# INCAM.net
KiCad netlist of a schematic drawn in Altium Designer
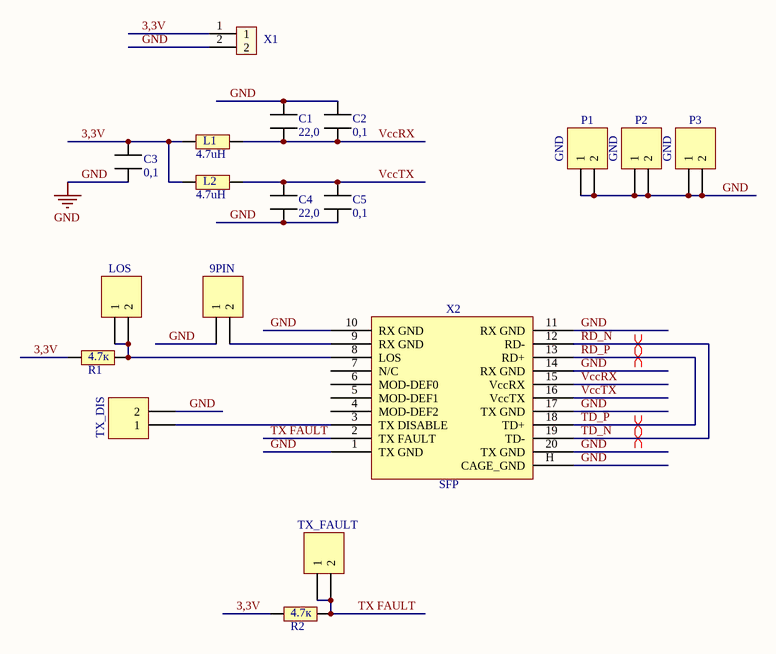
[diagram p0: INCAM.SchDoc]

(export (version "E")
  (design (tool "Eeschema 10.0.6"))
  (components
    (comp (ref "9PIN")
      (value "Header 2")
      (footprint "HDR1X2")
      (description "Header, 2-Pin")
      (fields (field (name "PUBLISHER") "Altium Limited"))
      (libsource (lib "Miscellaneous Connectors") (part "Header 2"))
    )
    (comp (ref "C1") (value "22,0") (footprint "Cap_BIG") (libsource (lib "Schlib") (part "CAP_BIG")))
    (comp (ref "C2") (value "0,1") (footprint "CAP_SMALL") (libsource (lib "Schlib") (part "CAP_SMALL")))
    (comp (ref "C3") (value "0,1") (footprint "CAP_SMALL") (libsource (lib "Schlib") (part "CAP_SMALL")))
    (comp (ref "C4") (value "22,0") (footprint "Cap_BIG") (libsource (lib "Schlib") (part "CAP_BIG")))
    (comp (ref "C5") (value "0,1") (footprint "CAP_SMALL") (libsource (lib "Schlib") (part "CAP_SMALL")))
    (comp (ref "L1") (value "4.7uH") (footprint "RES") (libsource (lib "Schlib") (part "RES")))
    (comp (ref "L2") (value "4.7uH") (footprint "RES") (libsource (lib "Schlib") (part "RES")))
    (comp (ref "LOS")
      (value "Header 2")
      (footprint "HDR1X2")
      (description "Header, 2-Pin")
      (fields (field (name "PUBLISHER") "Altium Limited"))
      (libsource (lib "Miscellaneous Connectors") (part "Header 2"))
    )
    (comp (ref "P1")
      (value "GND")
      (footprint "HDR1X2")
      (description "Header, 2-Pin")
      (fields (field (name "PUBLISHER") "Altium Limited"))
      (libsource (lib "Miscellaneous Connectors") (part "Header 2"))
    )
    (comp (ref "P2")
      (value "GND")
      (footprint "HDR1X2")
      (description "Header, 2-Pin")
      (fields (field (name "PUBLISHER") "Altium Limited"))
      (libsource (lib "Miscellaneous Connectors") (part "Header 2"))
    )
    (comp (ref "P3")
      (value "GND")
      (footprint "HDR1X2")
      (description "Header, 2-Pin")
      (fields (field (name "PUBLISHER") "Altium Limited"))
      (libsource (lib "Miscellaneous Connectors") (part "Header 2"))
    )
    (comp (ref "R1") (value "4.7к") (footprint "RES") (libsource (lib "Schlib") (part "RES")))
    (comp (ref "R2") (value "4.7к") (footprint "RES") (libsource (lib "Schlib") (part "RES")))
    (comp (ref "TX_DIS")
      (value "Header 2")
      (footprint "HDR1X2")
      (description "Header, 2-Pin")
      (fields (field (name "PUBLISHER") "Altium Limited"))
      (libsource (lib "") (part "Header 2_1"))
    )
    (comp (ref "TX_FAULT")
      (value "Header 2")
      (footprint "HDR1X2")
      (description "Header, 2-Pin")
      (fields (field (name "PUBLISHER") "Altium Limited"))
      (libsource (lib "Miscellaneous Connectors") (part "Header 2"))
    )
    (comp (ref "X1") (value "KL_2") (footprint "KLEMMNIK_2") (libsource (lib "Schlib") (part "KLEMMNIK_2")))
    (comp (ref "X2") (value "SFP") (footprint "SFP-20pin") (libsource (lib "MIT_Schlib") (part "SFP-20pin")))
  )
  (nets
    (net (code "1") (name "/3,3V") (class "Default")
      (node (ref "C3") (pin "2") (pinfunction "2_2") (pintype "passive"))
      (node (ref "L1") (pin "1") (pinfunction "1_1") (pintype "passive"))
      (node (ref "L2") (pin "1") (pinfunction "1_1") (pintype "passive"))
      (node (ref "R1") (pin "1") (pinfunction "1_1") (pintype "passive"))
      (node (ref "R2") (pin "1") (pinfunction "1_1") (pintype "passive"))
      (node (ref "X1") (pin "1") (pinfunction "1_1") (pintype "passive"))
    )
    (net (code "2") (name "/RD_N") (class "Default")
      (node (ref "X2") (pin "12") (pinfunction "RD-_12") (pintype "passive"))
      (node (ref "X2") (pin "19") (pinfunction "TD-_19") (pintype "passive"))
    )
    (net (code "3") (name "/RD_P") (class "Default")
      (node (ref "X2") (pin "13") (pinfunction "RD+_13") (pintype "passive"))
      (node (ref "X2") (pin "18") (pinfunction "TD+_18") (pintype "passive"))
    )
    (net (code "4") (name "/TX FAULT") (class "Default")
      (node (ref "R2") (pin "2") (pinfunction "2_2") (pintype "passive"))
      (node (ref "TX_FAULT") (pin "1") (pinfunction "1_1") (pintype "passive"))
      (node (ref "TX_FAULT") (pin "2") (pinfunction "2_2") (pintype "passive"))
      (node (ref "X2") (pin "2") (pinfunction "TX_FAULT_2") (pintype "passive"))
    )
    (net (code "5") (name "/VccRX") (class "Default")
      (node (ref "C1") (pin "1") (pinfunction "1_1") (pintype "passive"))
      (node (ref "C2") (pin "1") (pinfunction "1_1") (pintype "passive"))
      (node (ref "L1") (pin "2") (pinfunction "2_2") (pintype "passive"))
      (node (ref "X2") (pin "15") (pinfunction "VccRX_15") (pintype "passive"))
    )
    (net (code "6") (name "/VccTX") (class "Default")
      (node (ref "C4") (pin "2") (pinfunction "2_2") (pintype "passive"))
      (node (ref "C5") (pin "2") (pinfunction "2_2") (pintype "passive"))
      (node (ref "L2") (pin "2") (pinfunction "2_2") (pintype "passive"))
      (node (ref "X2") (pin "16") (pinfunction "VccTX_16") (pintype "passive"))
    )
    (net (code "7") (name "GND") (class "Default")
      (node (ref "9PIN") (pin "1") (pinfunction "1_1") (pintype "passive"))
      (node (ref "C1") (pin "2") (pinfunction "2_2") (pintype "passive"))
      (node (ref "C2") (pin "2") (pinfunction "2_2") (pintype "passive"))
      (node (ref "C3") (pin "1") (pinfunction "1_1") (pintype "passive"))
      (node (ref "C4") (pin "1") (pinfunction "1_1") (pintype "passive"))
      (node (ref "C5") (pin "1") (pinfunction "1_1") (pintype "passive"))
      (node (ref "P1") (pin "1") (pinfunction "1_1") (pintype "passive"))
      (node (ref "P1") (pin "2") (pinfunction "2_2") (pintype "passive"))
      (node (ref "P2") (pin "1") (pinfunction "1_1") (pintype "passive"))
      (node (ref "P2") (pin "2") (pinfunction "2_2") (pintype "passive"))
      (node (ref "P3") (pin "1") (pinfunction "1_1") (pintype "passive"))
      (node (ref "P3") (pin "2") (pinfunction "2_2") (pintype "passive"))
      (node (ref "TX_DIS") (pin "2") (pinfunction "2_2") (pintype "passive"))
      (node (ref "X1") (pin "2") (pinfunction "2_2") (pintype "passive"))
      (node (ref "X2") (pin "1") (pinfunction "TX_GND_1") (pintype "passive"))
      (node (ref "X2") (pin "10") (pinfunction "RX_GND_10") (pintype "passive"))
      (node (ref "X2") (pin "11") (pinfunction "RX_GND_11") (pintype "passive"))
      (node (ref "X2") (pin "14") (pinfunction "RX_GND_14") (pintype "passive"))
      (node (ref "X2") (pin "17") (pinfunction "TX_GND_17") (pintype "passive"))
      (node (ref "X2") (pin "20") (pinfunction "TX_GND_20") (pintype "passive"))
      (node (ref "X2") (pin "H") (pinfunction "CAGE_GND_H") (pintype "passive"))
    )
    (net (code "8") (name "Net-(9PIN-Pad2)") (class "Default")
      (node (ref "9PIN") (pin "2") (pinfunction "2_2") (pintype "passive"))
      (node (ref "X2") (pin "9") (pinfunction "RX_GND_9") (pintype "passive"))
    )
    (net (code "9") (name "Net-(X2-LOS)") (class "Default")
      (node (ref "LOS") (pin "1") (pinfunction "1_1") (pintype "passive"))
      (node (ref "LOS") (pin "2") (pinfunction "2_2") (pintype "passive"))
      (node (ref "R1") (pin "2") (pinfunction "2_2") (pintype "passive"))
      (node (ref "X2") (pin "8") (pinfunction "LOS_8") (pintype "passive"))
    )
    (net (code "10") (name "Net-(X2-TX_DISABLE)") (class "Default")
      (node (ref "TX_DIS") (pin "1") (pinfunction "1_1") (pintype "passive"))
      (node (ref "X2") (pin "3") (pinfunction "TX_DISABLE_3") (pintype "passive"))
    )
    (net (code "11") (name "unconnected-(X2-MOD-DEF0-Pad6)") (class "Default")
      (node (ref "X2") (pin "6") (pinfunction "MOD-DEF0_6") (pintype "passive"))
    )
    (net (code "12") (name "unconnected-(X2-MOD-DEF1-Pad5)") (class "Default")
      (node (ref "X2") (pin "5") (pinfunction "MOD-DEF1_5") (pintype "passive"))
    )
    (net (code "13") (name "unconnected-(X2-MOD-DEF2-Pad4)") (class "Default")
      (node (ref "X2") (pin "4") (pinfunction "MOD-DEF2_4") (pintype "passive"))
    )
    (net (code "14") (name "unconnected-(X2-N{slash}C-Pad7)") (class "Default")
      (node (ref "X2") (pin "7") (pinfunction "N/C_7") (pintype "passive"))
    )
  )
)
